# 14_-_SPI_FLASH_LEDS.net
KiCad netlist of a schematic drawn in Altium Designer
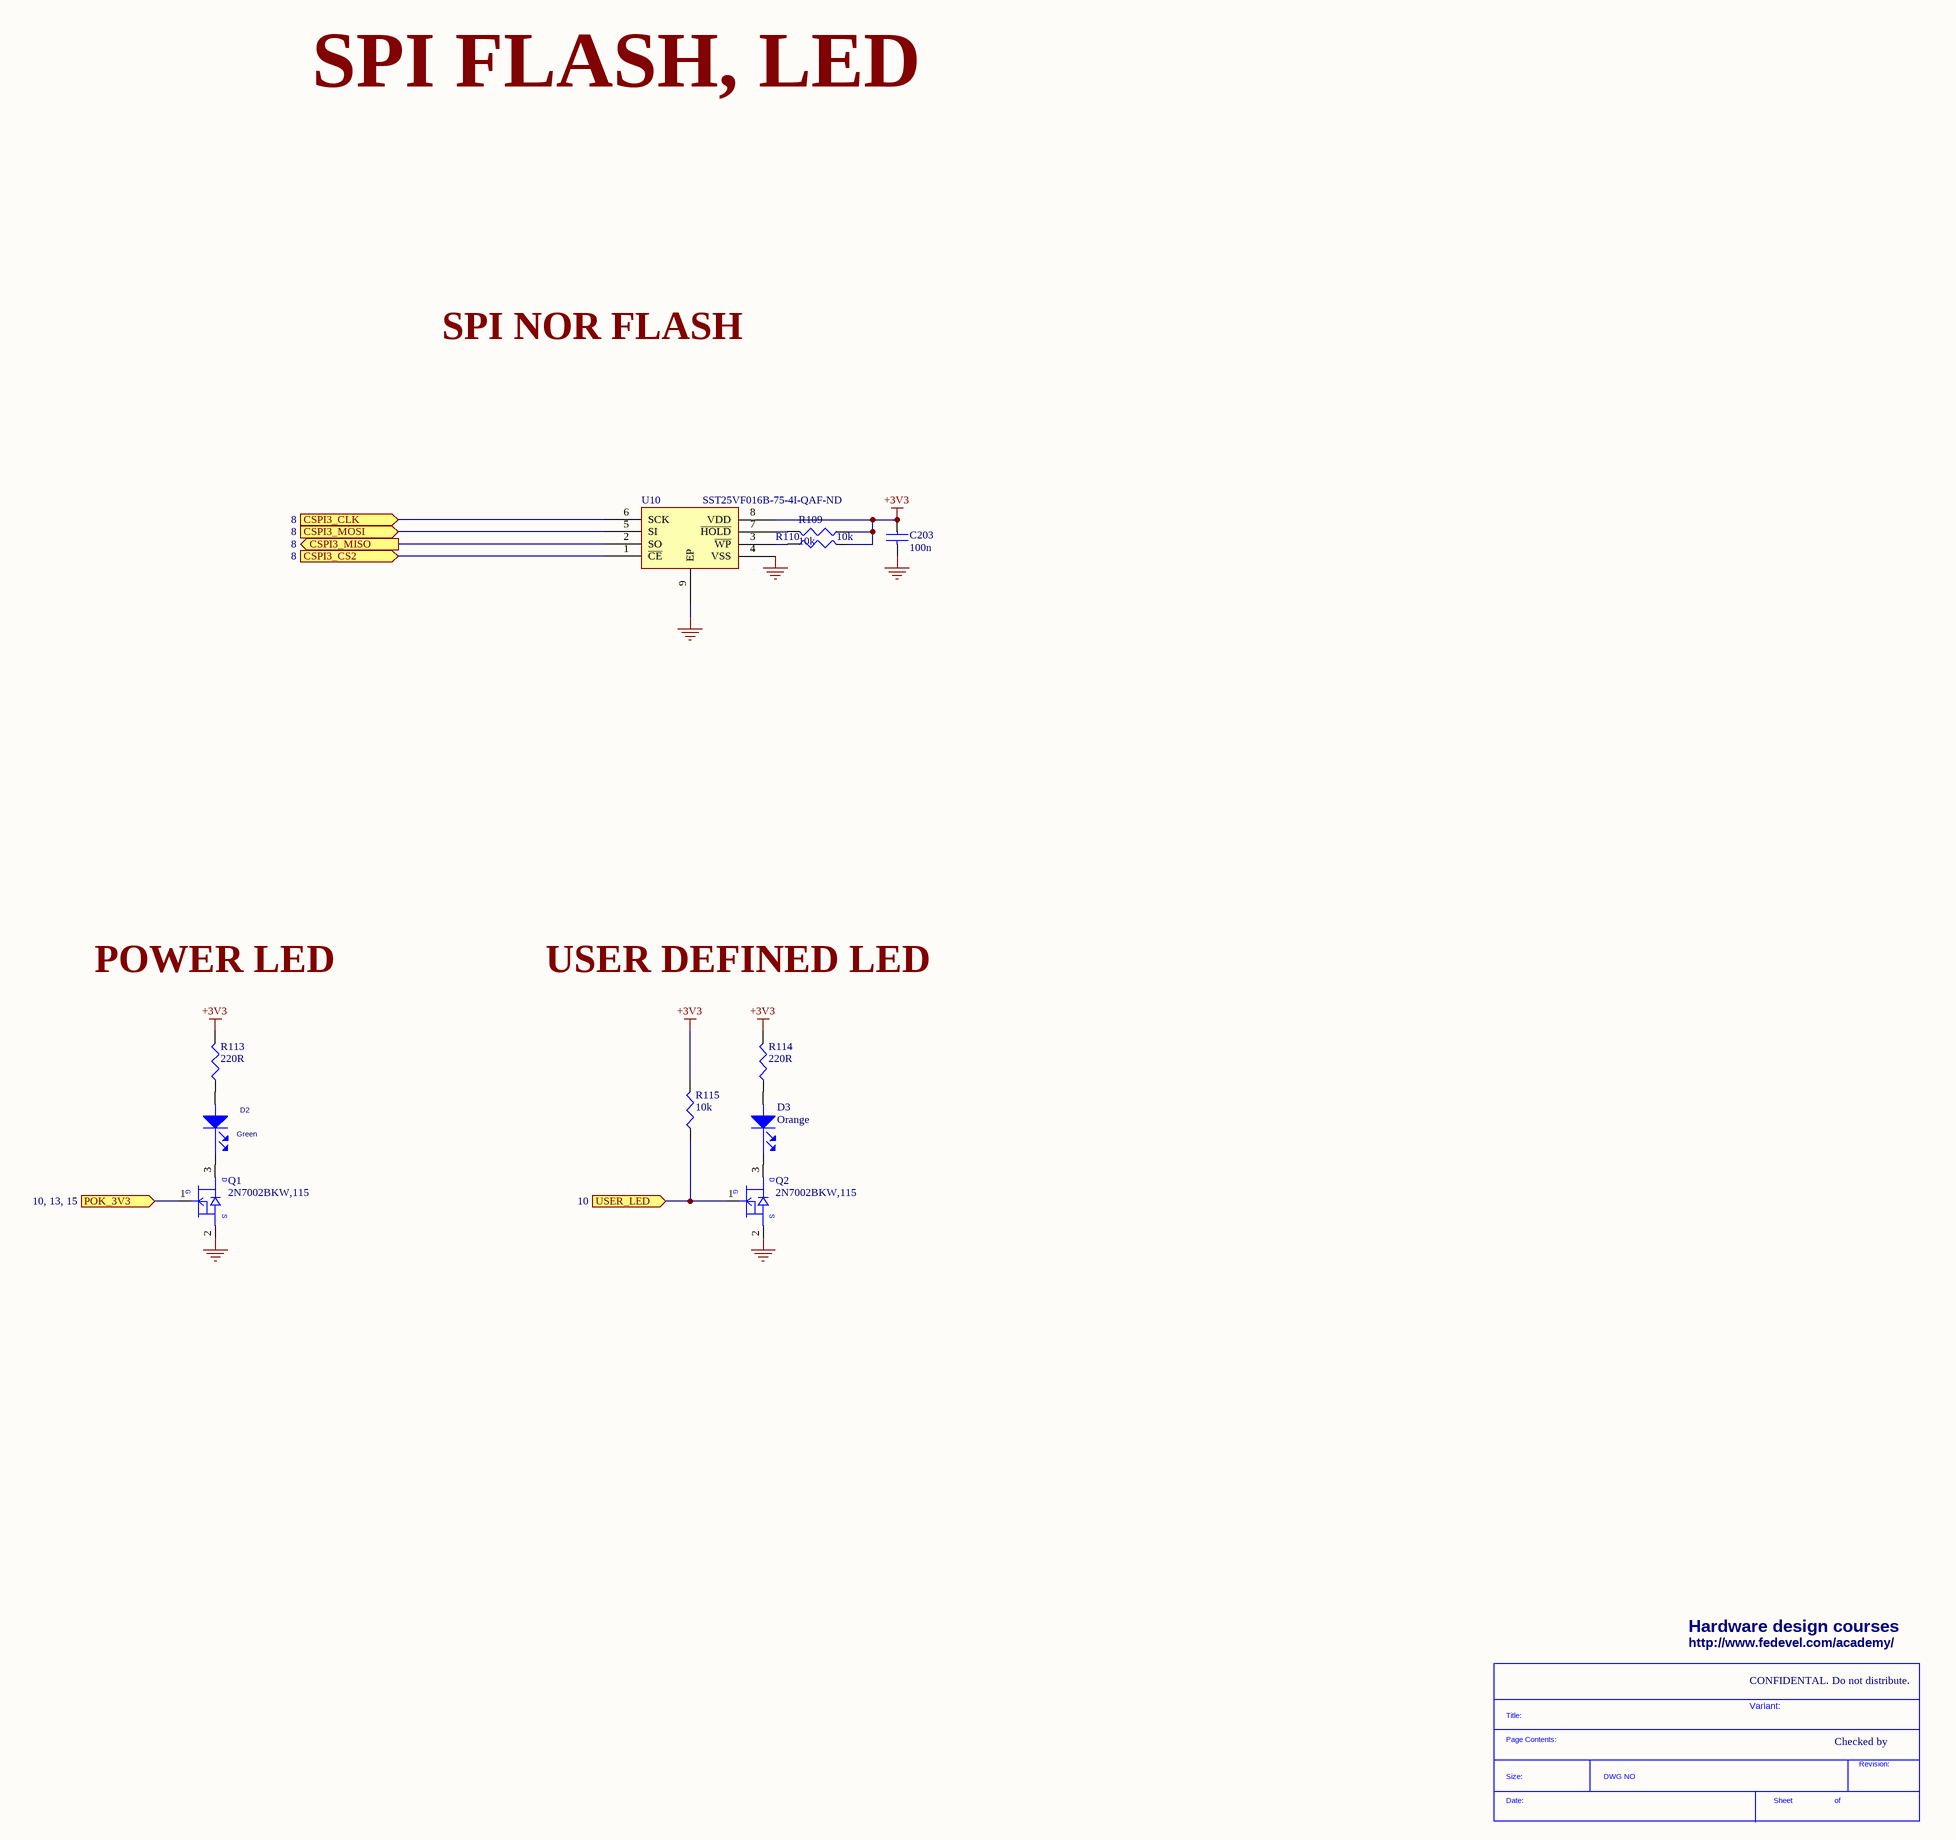
[diagram p0: [14] - SPI FLASH, LEDS.SchDoc]

(export (version "E")
  (design (tool "Eeschema 10.0.6"))
  (components
    (comp (ref "C203")
      (value "100n")
      (footprint "C0402")
      (description "CAP CER .10UF 50V X5R 10% 0402")
      (fields
        (field (name "MANUFACTURER") "TDK Corporation")
        (field (name "MANUFACTURER PART NUMBER") "C1005X5R1H104K")
      )
      (libsource (lib "iMX6 Rex_V1I1") (part "C1005X5R1H104K"))
    )
    (comp (ref "D2")
      (value "Green")
      (footprint "LED_0603")
      (description "LED SMARTLED GREEN 570NM 0603")
      (fields
        (field (name "MANUFACTURER") "OSRAM Opto Semiconductors Inc")
        (field (name "MANUFACTURER PART NUMBER") "LG L29K-G2J1-24-Z")
      )
      (libsource (lib "iMX6 Rex_V1I1") (part "LG L29K-G2J1-24-Z"))
    )
    (comp (ref "D3")
      (value "Orange")
      (footprint "LED_0603")
      (description "LED SMARTLED ORANGE 606NM 0603")
      (fields
        (field (name "MANUFACTURER") "OSRAM Opto Semiconductors Inc")
        (field (name "MANUFACTURER PART NUMBER") "LO L29K-H2K1-24-Z")
        (field (name ".CHECKED PCB") "RF")
        (field (name ".CHECKED SCH") "RF")
      )
      (libsource (lib "iMX6 Rex_V1I1") (part "LO L29K-H2K1-24-Z"))
    )
    (comp (ref "Q1")
      (value "2N7002BKW,115")
      (footprint "SC70_SOT323")
      (description "MOSFET N-CH 60V 310MA SOT323")
      (fields
        (field (name "MANUFACTURER") "NXP Semiconductors")
        (field (name ".CHECKED PCB") "RF")
        (field (name ".CHECKED SCH") "RF")
      )
      (libsource (lib "iMX6 Rex_V1I1") (part "2N7002BKW,115"))
    )
    (comp (ref "Q2")
      (value "2N7002BKW,115")
      (footprint "SC70_SOT323")
      (description "MOSFET N-CH 60V 310MA SOT323")
      (fields
        (field (name "MANUFACTURER") "NXP Semiconductors")
        (field (name ".CHECKED PCB") "RF")
        (field (name ".CHECKED SCH") "RF")
      )
      (libsource (lib "iMX6 Rex_V1I1") (part "2N7002BKW,115"))
    )
    (comp (ref "R109")
      (value "10k")
      (footprint "R0402")
      (description "RES 10.0K OHM 1/16W 1% 0402 SMD")
      (fields
        (field (name "MANUFACTURER") "Yageo")
        (field (name "MANUFACTURER PART NUMBER") "RC0402FR-0710KL")
      )
      (libsource (lib "iMX6 Rex_V1I1") (part "RC0402FR-0710KL"))
    )
    (comp (ref "R110")
      (value "10k")
      (footprint "R0402")
      (description "RES 10.0K OHM 1/16W 1% 0402 SMD")
      (fields
        (field (name "MANUFACTURER") "Yageo")
        (field (name "MANUFACTURER PART NUMBER") "RC0402FR-0710KL")
      )
      (libsource (lib "iMX6 Rex_V1I1") (part "RC0402FR-0710KL"))
    )
    (comp (ref "R113")
      (value "220R")
      (footprint "R0402")
      (description "RES 220 OHM 1/16W 1% 0402 SMD")
      (fields
        (field (name "MANUFACTURER") "Yageo")
        (field (name "MANUFACTURER PART NUMBER") "RC0402FR-07220RL")
      )
      (libsource (lib "iMX6 Rex_V1I1") (part "RC0402FR-07220RL"))
    )
    (comp (ref "R114")
      (value "220R")
      (footprint "R0402")
      (description "RES 220 OHM 1/16W 1% 0402 SMD")
      (fields
        (field (name "MANUFACTURER") "Yageo")
        (field (name "MANUFACTURER PART NUMBER") "RC0402FR-07220RL")
      )
      (libsource (lib "iMX6 Rex_V1I1") (part "RC0402FR-07220RL"))
    )
    (comp (ref "R115")
      (value "10k")
      (footprint "R0402")
      (description "RES 10.0K OHM 1/16W 1% 0402 SMD")
      (fields
        (field (name "MANUFACTURER") "Yageo")
        (field (name "MANUFACTURER PART NUMBER") "RC0402FR-0710KL")
      )
      (libsource (lib "iMX6 Rex_V1I1") (part "RC0402FR-0710KL"))
    )
    (comp (ref "U10")
      (value "SST25VF016B-75-4I-QAF-ND")
      (footprint "WSON8_6X5MM")
      (description "IC FLASH 16MBIT 75MHZ 8WSON")
      (fields
        (field (name "MANUFACTURER") "Microchip Technology")
        (field (name "MANUFACTURER PART NUMBER") "SST25VF016B-75-4I-QAF")
        (field (name ".CREATOR") "MM")
        (field (name ".CHECKED PCB") "MM, checked by RF")
        (field (name ".CHECKED SCH") "MM, checked by RF")
      )
      (libsource (lib "iMX6 Rex_V1I1") (part "SST25VF016B-75-4I-QAF"))
    )
  )
  (nets
    (net (code "1") (name "+3V3") (class "Default")
      (node (ref "C203") (pin "1") (pinfunction "1_1") (pintype "passive"))
      (node (ref "R109") (pin "1") (pinfunction "1_1") (pintype "passive"))
      (node (ref "R110") (pin "2") (pinfunction "2_2") (pintype "passive"))
      (node (ref "R113") (pin "2") (pinfunction "2_2") (pintype "passive"))
      (node (ref "R114") (pin "2") (pinfunction "2_2") (pintype "passive"))
      (node (ref "R115") (pin "2") (pinfunction "2_2") (pintype "passive"))
      (node (ref "U10") (pin "8") (pinfunction "VDD_8") (pintype "passive"))
    )
    (net (code "2") (name "/CSPI3_CLK") (class "Default")
      (node (ref "U10") (pin "6") (pinfunction "SCK_6") (pintype "passive"))
    )
    (net (code "3") (name "/CSPI3_CS2") (class "Default")
      (node (ref "U10") (pin "1") (pinfunction "~{CE}_1") (pintype "passive"))
    )
    (net (code "4") (name "/CSPI3_MISO") (class "Default")
      (node (ref "U10") (pin "2") (pinfunction "SO_2") (pintype "passive"))
    )
    (net (code "5") (name "/CSPI3_MOSI") (class "Default")
      (node (ref "U10") (pin "5") (pinfunction "SI_5") (pintype "passive"))
    )
    (net (code "6") (name "/POK_3V3") (class "Default")
      (node (ref "Q1") (pin "1") (pinfunction "GATE_1") (pintype "passive"))
    )
    (net (code "7") (name "/USER_LED") (class "Default")
      (node (ref "Q2") (pin "1") (pinfunction "GATE_1") (pintype "passive"))
      (node (ref "R115") (pin "1") (pinfunction "1_1") (pintype "passive"))
    )
    (net (code "8") (name "GND") (class "Default")
      (node (ref "C203") (pin "2") (pinfunction "2_2") (pintype "passive"))
      (node (ref "Q1") (pin "2") (pinfunction "SOURCE_2") (pintype "passive"))
      (node (ref "Q2") (pin "2") (pinfunction "SOURCE_2") (pintype "passive"))
      (node (ref "U10") (pin "4") (pinfunction "VSS_4") (pintype "passive"))
      (node (ref "U10") (pin "9") (pinfunction "EP_9") (pintype "passive"))
    )
    (net (code "9") (name "Net-(D2-ANODE)") (class "Default")
      (node (ref "D2") (pin "2") (pinfunction "ANODE_2") (pintype "passive"))
      (node (ref "R113") (pin "1") (pinfunction "1_1") (pintype "passive"))
    )
    (net (code "10") (name "Net-(D2-cathode)") (class "Default")
      (node (ref "D2") (pin "1") (pinfunction "cathode_1") (pintype "passive"))
      (node (ref "Q1") (pin "3") (pinfunction "DRAIN_3") (pintype "passive"))
    )
    (net (code "11") (name "Net-(D3-ANODE)") (class "Default")
      (node (ref "D3") (pin "2") (pinfunction "ANODE_2") (pintype "passive"))
      (node (ref "R114") (pin "1") (pinfunction "1_1") (pintype "passive"))
    )
    (net (code "12") (name "Net-(D3-cathode)") (class "Default")
      (node (ref "D3") (pin "1") (pinfunction "cathode_1") (pintype "passive"))
      (node (ref "Q2") (pin "3") (pinfunction "DRAIN_3") (pintype "passive"))
    )
    (net (code "13") (name "Net-(U10-~{HOLD})") (class "Default")
      (node (ref "R109") (pin "2") (pinfunction "2_2") (pintype "passive"))
      (node (ref "U10") (pin "7") (pinfunction "~{HOLD}_7") (pintype "passive"))
    )
    (net (code "14") (name "Net-(U10-~{WP})") (class "Default")
      (node (ref "R110") (pin "1") (pinfunction "1_1") (pintype "passive"))
      (node (ref "U10") (pin "3") (pinfunction "~{WP}_3") (pintype "passive"))
    )
  )
)
